# CONTROL_PCB_MAIN.net
KiCad netlist of a schematic drawn in Altium Designer
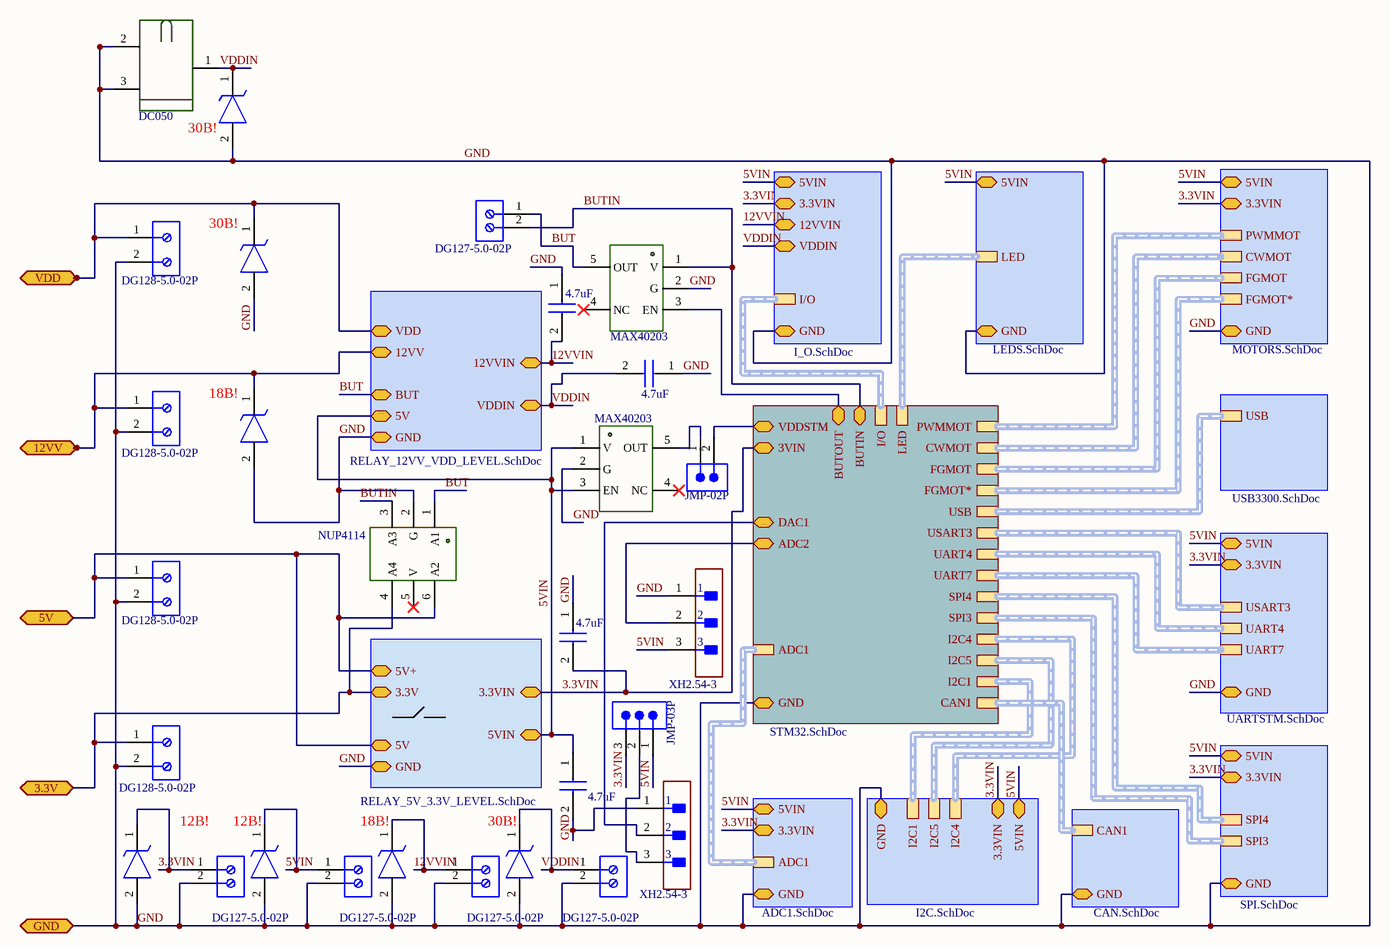
[diagram p0: CONTROL_PCB_MAIN.SchDoc]

(export (version "E")
  (design (tool "Eeschema 10.0.6"))
  (components
    (comp (ref "CAP3.3VIN")
      (value "4.7uF")
      (footprint "CAP0805")
      (description "CAP-SMD0805")
      (libsource (lib "Components_Robots") (part "CAP0805"))
    )
    (comp (ref "CAP5VIN")
      (value "4.7uF")
      (footprint "CAP0805")
      (description "CAP-SMD0805")
      (libsource (lib "Components_Robots") (part "CAP0805"))
    )
    (comp (ref "CAP12VVIN")
      (value "4.7uF")
      (footprint "CAP0805")
      (description "CAP-SMD0805")
      (libsource (lib "Components_Robots") (part "CAP0805"))
    )
    (comp (ref "CAPVDDIN")
      (value "4.7uF")
      (footprint "CAP0805")
      (description "CAP-SMD0805")
      (libsource (lib "Components_Robots") (part "CAP0805"))
    )
    (comp (ref "DC050_VDD")
      (value "DC050")
      (footprint "DC050")
      (description "DC050-T")
      (libsource (lib "Components_Robots") (part "DC050"))
    )
    (comp (ref "DGBUT")
      (value "DG127-5.0-02P")
      (footprint "DG127-5.0-02P")
      (description "DG127-5.0-02P-14-00Z")
      (libsource (lib "Components_Robots") (part "DG127-5.0-02P"))
    )
    (comp (ref "DGIN3.3V2")
      (value "DG128-5.0-02P")
      (footprint "DG128-5.0-02P")
      (description "DG128-5.0-02P-14")
      (libsource (lib "Components_Robots") (part "DG128-5.0-02P"))
    )
    (comp (ref "DGIN5V2")
      (value "DG128-5.0-02P")
      (footprint "DG128-5.0-02P")
      (description "DG128-5.0-02P-14")
      (libsource (lib "Components_Robots") (part "DG128-5.0-02P"))
    )
    (comp (ref "DGIN12VV2")
      (value "DG128-5.0-02P")
      (footprint "DG128-5.0-02P")
      (description "DG128-5.0-02P-14")
      (libsource (lib "Components_Robots") (part "DG128-5.0-02P"))
    )
    (comp (ref "DGOUT3.3V")
      (value "DG127-5.0-02P")
      (footprint "DG127-5.0-02P")
      (description "DG127-5.0-02P-14-00Z")
      (libsource (lib "Components_Robots") (part "DG127-5.0-02P"))
    )
    (comp (ref "DGOUT5V")
      (value "DG127-5.0-02P")
      (footprint "DG127-5.0-02P")
      (description "DG127-5.0-02P-14-00Z")
      (libsource (lib "Components_Robots") (part "DG127-5.0-02P"))
    )
    (comp (ref "DGOUT12VV")
      (value "DG127-5.0-02P")
      (footprint "DG127-5.0-02P")
      (description "DG127-5.0-02P-14-00Z")
      (libsource (lib "Components_Robots") (part "DG127-5.0-02P"))
    )
    (comp (ref "DGOUTVDD")
      (value "DG127-5.0-02P")
      (footprint "DG127-5.0-02P")
      (description "DG127-5.0-02P-14-00Z")
      (libsource (lib "Components_Robots") (part "DG127-5.0-02P"))
    )
    (comp (ref "DGVDD2")
      (value "DG128-5.0-02P")
      (footprint "DG128-5.0-02P")
      (description "DG128-5.0-02P-14")
      (libsource (lib "Components_Robots") (part "DG128-5.0-02P"))
    )
    (comp (ref "ESD12VV")
      (value "SM6T30A")
      (footprint "SM6T-A")
      (description "SM6T12A-SMD")
      (libsource (lib "Components_Robots") (part "SM6T-A"))
    )
    (comp (ref "ESDOUT3V")
      (value "SM6T30A")
      (footprint "SM6T-A")
      (description "SM6T12A-SMD")
      (libsource (lib "Components_Robots") (part "SM6T-A"))
    )
    (comp (ref "ESDOUT5V")
      (value "SM6T30A")
      (footprint "SM6T-A")
      (description "SM6T12A-SMD")
      (libsource (lib "Components_Robots") (part "SM6T-A"))
    )
    (comp (ref "ESDOUT12V")
      (value "SM6T30A")
      (footprint "SM6T-A")
      (description "SM6T12A-SMD")
      (libsource (lib "Components_Robots") (part "SM6T-A"))
    )
    (comp (ref "ESDOUTVDD")
      (value "SM6T30A")
      (footprint "SM6T-A")
      (description "SM6T12A-SMD")
      (libsource (lib "Components_Robots") (part "SM6T-A"))
    )
    (comp (ref "ESDPLUG_VDD")
      (value "SM6T30A")
      (footprint "SM6T-A")
      (description "SM6T12A-SMD")
      (libsource (lib "Components_Robots") (part "SM6T-A"))
    )
    (comp (ref "ESDVDD")
      (value "SM6T30A")
      (footprint "SM6T-A")
      (description "SM6T12A-SMD")
      (libsource (lib "Components_Robots") (part "SM6T-A"))
    )
    (comp (ref "JMPDC1")
      (value "JMP-03P")
      (footprint "JMP-03P")
      (description "PLS-1x3")
      (libsource (lib "Components_Robots") (part "JMP-03P"))
    )
    (comp (ref "JMPSTM5V")
      (value "JMP-02P")
      (footprint "JMP-02P")
      (description "PLS-1x2")
      (libsource (lib "Components_Robots") (part "JMP-02P"))
    )
    (comp (ref "MAX5VSTM")
      (value "MAX40203")
      (footprint "MAX40203")
      (description "MAX40203AUK+T")
      (libsource (lib "Components_Robots") (part "MAX40203"))
    )
    (comp (ref "MAXBUT")
      (value "MAX40203")
      (footprint "MAX40203")
      (description "MAX40203AUK+T")
      (libsource (lib "") (part "MAX40203_1"))
    )
    (comp (ref "NUPIN")
      (value "NUP4114")
      (footprint "NUP4114")
      (description "NUP4114HMR6T1G")
      (libsource (lib "Components_Robots") (part "NUP4114"))
    )
    (comp (ref "XHADC2")
      (value "XH2.54-3")
      (footprint "XH2.54-3")
      (description "JST XH2.54-3pin")
      (libsource (lib "Components_Robots") (part "XH2.54-3"))
    )
    (comp (ref "XHDAC1")
      (value "XH2.54-3")
      (footprint "XH2.54-3")
      (description "JST XH2.54-3pin")
      (libsource (lib "Components_Robots") (part "XH2.54-3"))
    )
  )
  (nets
    (net (code "1") (name "/3.3V") (class "Default")
      (node (ref "DGIN3.3V2") (pin "1") (pinfunction "1_1") (pintype "passive"))
      (node (ref "NUPIN") (pin "4") (pinfunction "A4_4") (pintype "passive"))
    )
    (net (code "2") (name "/3.3VIN") (class "Default")
      (node (ref "CAP3.3VIN") (pin "2") (pinfunction "2_2") (pintype "passive"))
      (node (ref "DGOUT3.3V") (pin "1") (pinfunction "1_1") (pintype "passive"))
      (node (ref "ESDOUT3V") (pin "1") (pinfunction "1_1") (pintype "passive"))
      (node (ref "JMPDC1") (pin "3") (pinfunction "3_3") (pintype "passive"))
    )
    (net (code "3") (name "/5V") (class "Default")
      (node (ref "DGIN5V2") (pin "1") (pinfunction "1_1") (pintype "passive"))
      (node (ref "NUPIN") (pin "6") (pinfunction "A2_6") (pintype "passive"))
    )
    (net (code "4") (name "/5VIN") (class "Default")
      (node (ref "CAP5VIN") (pin "1") (pinfunction "1_1") (pintype "passive"))
      (node (ref "DGOUT5V") (pin "1") (pinfunction "1_1") (pintype "passive"))
      (node (ref "ESDOUT5V") (pin "1") (pinfunction "1_1") (pintype "passive"))
      (node (ref "JMPDC1") (pin "1") (pinfunction "1_1") (pintype "passive"))
      (node (ref "MAX5VSTM") (pin "1") (pinfunction "V_1") (pintype "passive"))
      (node (ref "MAX5VSTM") (pin "3") (pinfunction "EN_3") (pintype "passive"))
      (node (ref "XHADC2") (pin "3") (pinfunction "3_3") (pintype "passive"))
    )
    (net (code "5") (name "/12VV") (class "Default")
      (node (ref "DGIN12VV2") (pin "1") (pinfunction "1_1") (pintype "passive"))
      (node (ref "ESD12VV") (pin "1") (pinfunction "1_1") (pintype "passive"))
    )
    (net (code "6") (name "/12VVIN") (class "Default")
      (node (ref "CAP12VVIN") (pin "2") (pinfunction "2_2") (pintype "passive"))
      (node (ref "DGOUT12VV") (pin "1") (pinfunction "1_1") (pintype "passive"))
      (node (ref "ESDOUT12V") (pin "1") (pinfunction "1_1") (pintype "passive"))
    )
    (net (code "8") (name "/ADC2") (class "Default")
      (node (ref "XHADC2") (pin "2") (pinfunction "2_2") (pintype "passive"))
    )
    (net (code "9") (name "/BUT") (class "Default")
      (node (ref "DGBUT") (pin "1") (pinfunction "1_1") (pintype "passive"))
      (node (ref "MAXBUT") (pin "5") (pinfunction "OUT_5") (pintype "passive"))
      (node (ref "NUPIN") (pin "1") (pinfunction "A1_1") (pintype "passive"))
    )
    (net (code "10") (name "/BUTIN") (class "Default")
      (node (ref "DGBUT") (pin "2") (pinfunction "2_2") (pintype "passive"))
      (node (ref "MAXBUT") (pin "1") (pinfunction "V_1") (pintype "passive"))
      (node (ref "NUPIN") (pin "3") (pinfunction "A3_3") (pintype "passive"))
    )
    (net (code "11") (name "/BUTOUT") (class "Default")
      (node (ref "MAXBUT") (pin "3") (pinfunction "EN_3") (pintype "passive"))
    )
    (net (code "14") (name "/DAC1") (class "Default")
      (node (ref "XHDAC1") (pin "2") (pinfunction "2_2") (pintype "passive"))
    )
    (net (code "17") (name "/GND") (class "Default")
      (node (ref "CAP12VVIN") (pin "1") (pinfunction "1_1") (pintype "passive"))
      (node (ref "CAP3.3VIN") (pin "1") (pinfunction "1_1") (pintype "passive"))
      (node (ref "CAP5VIN") (pin "2") (pinfunction "2_2") (pintype "passive"))
      (node (ref "CAPVDDIN") (pin "1") (pinfunction "1_1") (pintype "passive"))
      (node (ref "DC050_VDD") (pin "2") (pinfunction "2_2") (pintype "passive"))
      (node (ref "DC050_VDD") (pin "3") (pinfunction "3_3") (pintype "passive"))
      (node (ref "DGIN12VV2") (pin "2") (pinfunction "2_2") (pintype "passive"))
      (node (ref "DGIN3.3V2") (pin "2") (pinfunction "2_2") (pintype "passive"))
      (node (ref "DGIN5V2") (pin "2") (pinfunction "2_2") (pintype "passive"))
      (node (ref "DGOUT12VV") (pin "2") (pinfunction "2_2") (pintype "passive"))
      (node (ref "DGOUT3.3V") (pin "2") (pinfunction "2_2") (pintype "passive"))
      (node (ref "DGOUT5V") (pin "2") (pinfunction "2_2") (pintype "passive"))
      (node (ref "DGOUTVDD") (pin "2") (pinfunction "2_2") (pintype "passive"))
      (node (ref "DGVDD2") (pin "2") (pinfunction "2_2") (pintype "passive"))
      (node (ref "ESD12VV") (pin "2") (pinfunction "2_2") (pintype "passive"))
      (node (ref "ESDOUT12V") (pin "2") (pinfunction "2_2") (pintype "passive"))
      (node (ref "ESDOUT3V") (pin "2") (pinfunction "2_2") (pintype "passive"))
      (node (ref "ESDOUT5V") (pin "2") (pinfunction "2_2") (pintype "passive"))
      (node (ref "ESDOUTVDD") (pin "2") (pinfunction "2_2") (pintype "passive"))
      (node (ref "ESDPLUG_VDD") (pin "2") (pinfunction "2_2") (pintype "passive"))
      (node (ref "ESDVDD") (pin "2") (pinfunction "2_2") (pintype "passive"))
      (node (ref "MAX5VSTM") (pin "2") (pinfunction "G_2") (pintype "passive"))
      (node (ref "MAXBUT") (pin "2") (pinfunction "G_2") (pintype "passive"))
      (node (ref "NUPIN") (pin "2") (pinfunction "G_2") (pintype "passive"))
      (node (ref "XHADC2") (pin "1") (pinfunction "1_1") (pintype "passive"))
      (node (ref "XHDAC1") (pin "1") (pinfunction "1_1") (pintype "passive"))
    )
    (net (code "30") (name "/VDD") (class "Default")
      (node (ref "DGVDD2") (pin "1") (pinfunction "1_1") (pintype "passive"))
      (node (ref "ESDVDD") (pin "1") (pinfunction "1_1") (pintype "passive"))
    )
    (net (code "31") (name "/VDDIN") (class "Default")
      (node (ref "CAPVDDIN") (pin "2") (pinfunction "2_2") (pintype "passive"))
      (node (ref "DC050_VDD") (pin "1") (pinfunction "1_1") (pintype "passive"))
      (node (ref "DGOUTVDD") (pin "1") (pinfunction "1_1") (pintype "passive"))
      (node (ref "ESDOUTVDD") (pin "1") (pinfunction "1_1") (pintype "passive"))
      (node (ref "ESDPLUG_VDD") (pin "1") (pinfunction "1_1") (pintype "passive"))
    )
    (net (code "32") (name "/VDDSTM") (class "Default")
      (node (ref "JMPSTM5V") (pin "2") (pinfunction "2_2") (pintype "passive"))
    )
    (net (code "33") (name "Net-(JMPDC1-Pad2)") (class "Default")
      (node (ref "JMPDC1") (pin "2") (pinfunction "2_2") (pintype "passive"))
      (node (ref "XHDAC1") (pin "3") (pinfunction "3_3") (pintype "passive"))
    )
    (net (code "34") (name "Net-(MAX5VSTM-OUT)") (class "Default")
      (node (ref "JMPSTM5V") (pin "1") (pinfunction "1_1") (pintype "passive"))
      (node (ref "MAX5VSTM") (pin "5") (pinfunction "OUT_5") (pintype "passive"))
    )
    (net (code "35") (name "unconnected-(MAX5VSTM-NC-Pad4)") (class "Default")
      (node (ref "MAX5VSTM") (pin "4") (pinfunction "NC_4") (pintype "passive+no_connect"))
    )
    (net (code "36") (name "unconnected-(MAXBUT-NC-Pad4)") (class "Default")
      (node (ref "MAXBUT") (pin "4") (pinfunction "NC_4") (pintype "passive+no_connect"))
    )
    (net (code "37") (name "unconnected-(NUPIN-V-Pad5)") (class "Default")
      (node (ref "NUPIN") (pin "5") (pinfunction "V_5") (pintype "passive+no_connect"))
    )
  )
)
